# SX1308_GTW_e381v02c_RF_Part.net
KiCad netlist of a schematic drawn in Altium Designer
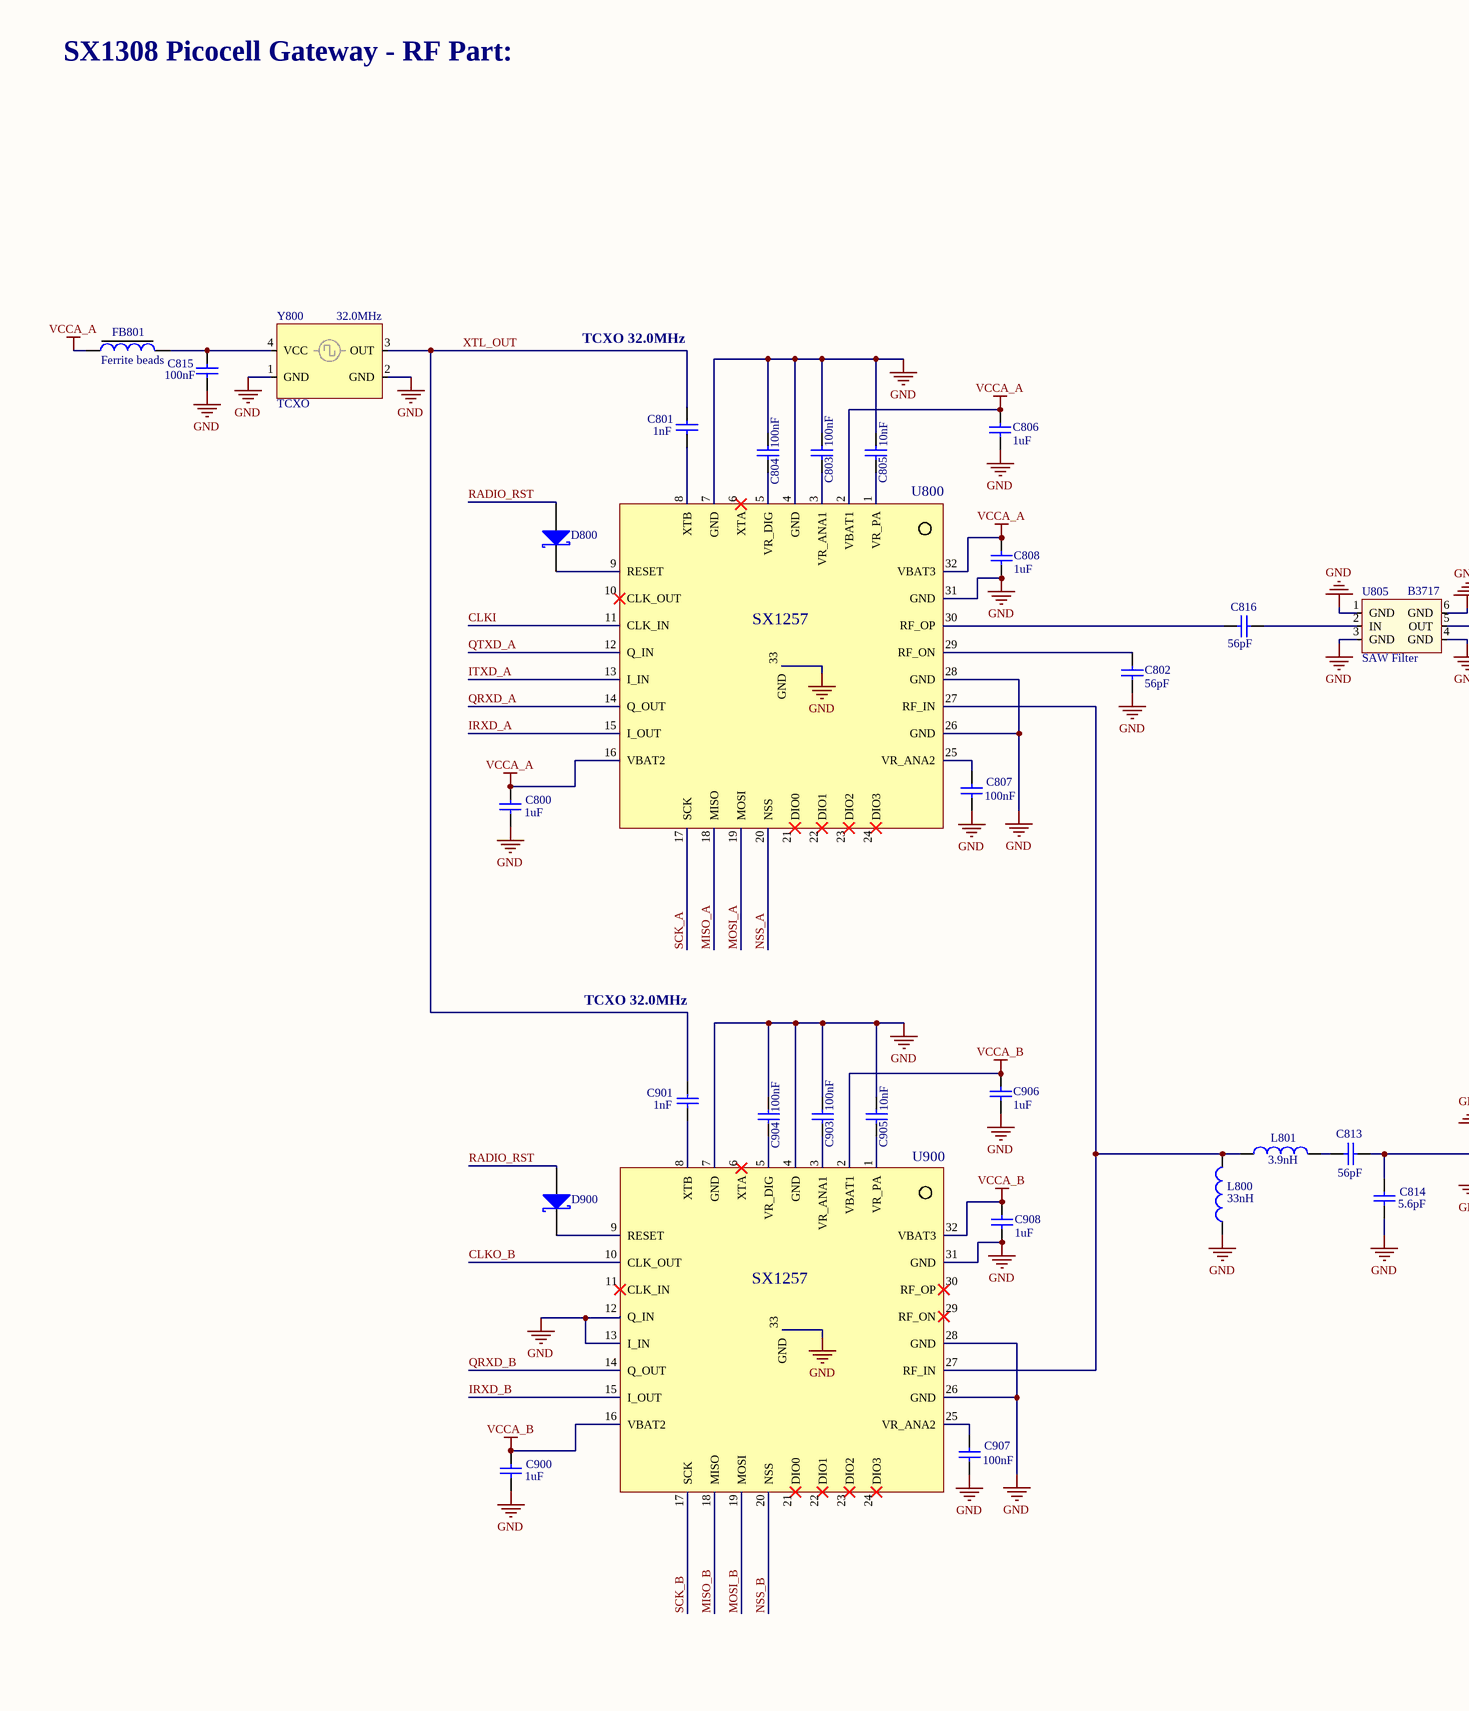
[diagram p0: SX1308_GTW_e381v02c_RF_Part.SchDoc, left]
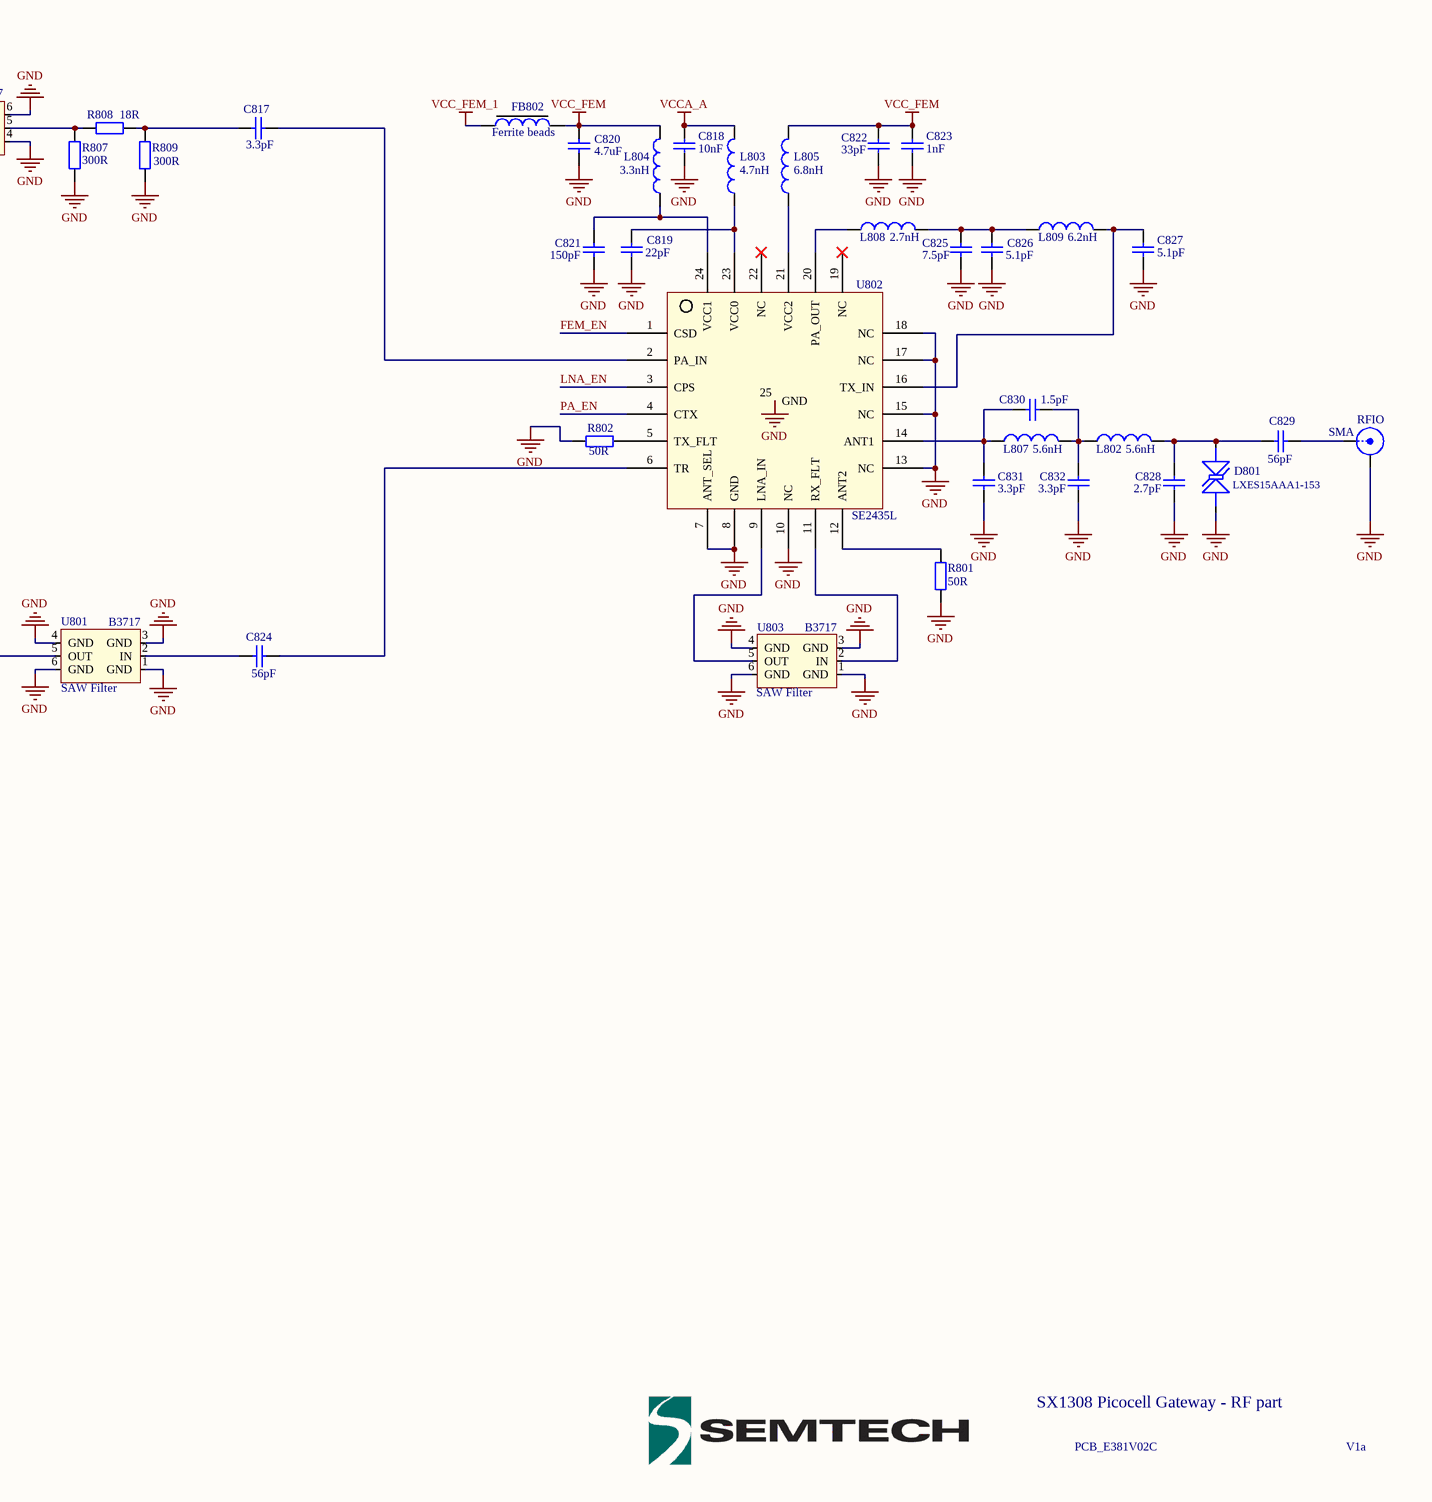
[diagram p1: SX1308_GTW_e381v02c_RF_Part.SchDoc, right]

(export (version "E")
  (design (tool "Eeschema 10.0.6"))
  (components
    (comp (ref "C800")
      (value "1uF")
      (footprint "rlc_603_smd")
      (description "Capacitor SMD")
      (fields (field (name "Comment") "Cap") (field (name "PUBLISHER") "Altium Limited"))
      (libsource (lib "SX1308_GTW_e381v02c") (part "Cap"))
    )
    (comp (ref "C801")
      (value "1nF")
      (footprint "rlc_402_smd")
      (description "Capacitor SMD")
      (fields (field (name "Comment") "Cap") (field (name "PUBLISHER") "Altium Limited"))
      (libsource (lib "SX1308_GTW_e381v02c") (part "Cap"))
    )
    (comp (ref "C802")
      (value "56pF")
      (footprint "rlc_402_smd")
      (description "Capacitor SMD")
      (fields (field (name "Comment") "Cap") (field (name "PUBLISHER") "Altium Limited"))
      (libsource (lib "SX1308_GTW_e381v02c") (part "Cap"))
    )
    (comp (ref "C803")
      (value "100nF")
      (footprint "rlc_402_smd")
      (description "Capacitor SMD")
      (fields (field (name "Comment") "Cap") (field (name "PUBLISHER") "Altium Limited"))
      (libsource (lib "SX1308_GTW_e381v02c") (part "Cap"))
    )
    (comp (ref "C804")
      (value "100nF")
      (footprint "rlc_402_smd")
      (description "Capacitor SMD")
      (fields (field (name "Comment") "Cap") (field (name "PUBLISHER") "Altium Limited"))
      (libsource (lib "SX1308_GTW_e381v02c") (part "Cap"))
    )
    (comp (ref "C805")
      (value "10nF")
      (footprint "rlc_402_smd")
      (description "Capacitor SMD")
      (fields (field (name "Comment") "Cap") (field (name "PUBLISHER") "Altium Limited"))
      (libsource (lib "SX1308_GTW_e381v02c") (part "Cap"))
    )
    (comp (ref "C806")
      (value "1uF")
      (footprint "rlc_603_smd")
      (description "Capacitor SMD")
      (fields (field (name "Comment") "Cap") (field (name "PUBLISHER") "Altium Limited"))
      (libsource (lib "SX1308_GTW_e381v02c") (part "Cap"))
    )
    (comp (ref "C807")
      (value "100nF")
      (footprint "rlc_402_smd")
      (description "Capacitor SMD")
      (fields (field (name "Comment") "Cap") (field (name "PUBLISHER") "Altium Limited"))
      (libsource (lib "SX1308_GTW_e381v02c") (part "Cap"))
    )
    (comp (ref "C808")
      (value "1uF")
      (footprint "rlc_603_smd")
      (description "Capacitor SMD")
      (fields (field (name "Comment") "Cap") (field (name "PUBLISHER") "Altium Limited"))
      (libsource (lib "SX1308_GTW_e381v02c") (part "Cap"))
    )
    (comp (ref "C813")
      (value "56pF")
      (footprint "rlc_402_smd")
      (description "Capacitor SMD")
      (fields (field (name "Comment") "Cap") (field (name "PUBLISHER") "Altium Limited"))
      (libsource (lib "SX1308_GTW_e381v02c") (part "Cap"))
    )
    (comp (ref "C814")
      (value "5.6pF")
      (footprint "rlc_402_smd")
      (description "Capacitor SMD")
      (fields (field (name "Comment") "Cap") (field (name "PUBLISHER") "Altium Limited"))
      (libsource (lib "SX1308_GTW_e381v02c") (part "Cap"))
    )
    (comp (ref "C815")
      (value "100nF")
      (footprint "rlc_402_smd")
      (description "Capacitor SMD")
      (fields (field (name "Comment") "Cap") (field (name "PUBLISHER") "Altium Limited"))
      (libsource (lib "SX1308_GTW_e381v02c") (part "Cap"))
    )
    (comp (ref "C816")
      (value "56pF")
      (footprint "rlc_402_smd")
      (description "Capacitor SMD")
      (fields (field (name "Comment") "Cap") (field (name "PUBLISHER") "Altium Limited"))
      (libsource (lib "SX1308_GTW_e381v02c") (part "Cap"))
    )
    (comp (ref "C817")
      (value "3.3pF")
      (footprint "rlc_402_smd")
      (description "Capacitor SMD")
      (fields (field (name "Comment") "Cap") (field (name "PUBLISHER") "Altium Limited"))
      (libsource (lib "SX1308_GTW_e381v02c") (part "Cap"))
    )
    (comp (ref "C818")
      (value "10nF")
      (footprint "rlc_402_smd")
      (description "Capacitor SMD")
      (fields (field (name "Comment") "Cap") (field (name "PUBLISHER") "Altium Limited"))
      (libsource (lib "SX1308_GTW_e381v02c") (part "Cap"))
    )
    (comp (ref "C819")
      (value "22pF")
      (footprint "rlc_402_smd")
      (description "Capacitor SMD")
      (fields (field (name "Comment") "Cap") (field (name "PUBLISHER") "Altium Limited"))
      (libsource (lib "SX1308_GTW_e381v02c") (part "Cap"))
    )
    (comp (ref "C820")
      (value "4.7uF")
      (footprint "rlc_603_smd")
      (description "Capacitor SMD")
      (fields (field (name "Comment") "Cap") (field (name "PUBLISHER") "Altium Limited"))
      (libsource (lib "SX1308_GTW_e381v02c") (part "Cap"))
    )
    (comp (ref "C821")
      (value "150pF")
      (footprint "rlc_402_smd")
      (description "Capacitor SMD")
      (fields (field (name "Comment") "Cap") (field (name "PUBLISHER") "Altium Limited"))
      (libsource (lib "SX1308_GTW_e381v02c") (part "Cap"))
    )
    (comp (ref "C822")
      (value "33pF")
      (footprint "rlc_402_smd")
      (description "Capacitor SMD")
      (fields (field (name "Comment") "Cap") (field (name "PUBLISHER") "Altium Limited"))
      (libsource (lib "SX1308_GTW_e381v02c") (part "Cap"))
    )
    (comp (ref "C823")
      (value "1nF")
      (footprint "rlc_402_smd")
      (description "Capacitor SMD")
      (fields (field (name "Comment") "Cap") (field (name "PUBLISHER") "Altium Limited"))
      (libsource (lib "SX1308_GTW_e381v02c") (part "Cap"))
    )
    (comp (ref "C824")
      (value "56pF")
      (footprint "rlc_402_smd")
      (description "Capacitor SMD")
      (fields (field (name "Comment") "Cap") (field (name "PUBLISHER") "Altium Limited"))
      (libsource (lib "SX1308_GTW_e381v02c") (part "Cap"))
    )
    (comp (ref "C825")
      (value "7.5pF")
      (footprint "rlc_402_smd")
      (description "Capacitor SMD")
      (fields (field (name "Comment") "Cap") (field (name "PUBLISHER") "Altium Limited"))
      (libsource (lib "SX1308_GTW_e381v02c") (part "Cap"))
    )
    (comp (ref "C826")
      (value "5.1pF")
      (footprint "rlc_402_smd")
      (description "Capacitor SMD")
      (fields (field (name "Comment") "Cap") (field (name "PUBLISHER") "Altium Limited"))
      (libsource (lib "SX1308_GTW_e381v02c") (part "Cap"))
    )
    (comp (ref "C827")
      (value "5.1pF")
      (footprint "rlc_402_smd")
      (description "Capacitor SMD")
      (fields (field (name "Comment") "Cap") (field (name "PUBLISHER") "Altium Limited"))
      (libsource (lib "SX1308_GTW_e381v02c") (part "Cap"))
    )
    (comp (ref "C828")
      (value "2.7pF")
      (footprint "rlc_402_smd")
      (description "Capacitor SMD")
      (fields (field (name "Comment") "Cap") (field (name "PUBLISHER") "Altium Limited"))
      (libsource (lib "SX1308_GTW_e381v02c") (part "Cap"))
    )
    (comp (ref "C829")
      (value "56pF")
      (footprint "rlc_402_smd")
      (description "Capacitor SMD")
      (fields (field (name "Comment") "Cap") (field (name "PUBLISHER") "Altium Limited"))
      (libsource (lib "SX1308_GTW_e381v02c") (part "Cap"))
    )
    (comp (ref "C830")
      (value "1.5pF")
      (footprint "rlc_402_smd")
      (description "Capacitor SMD")
      (fields (field (name "Comment") "Cap") (field (name "PUBLISHER") "Altium Limited"))
      (libsource (lib "SX1308_GTW_e381v02c") (part "Cap"))
    )
    (comp (ref "C831")
      (value "3.3pF")
      (footprint "rlc_402_smd")
      (description "Capacitor SMD")
      (fields (field (name "Comment") "Cap") (field (name "PUBLISHER") "Altium Limited"))
      (libsource (lib "SX1308_GTW_e381v02c") (part "Cap"))
    )
    (comp (ref "C832")
      (value "3.3pF")
      (footprint "rlc_402_smd")
      (description "Capacitor SMD")
      (fields (field (name "Comment") "Cap") (field (name "PUBLISHER") "Altium Limited"))
      (libsource (lib "SX1308_GTW_e381v02c") (part "Cap"))
    )
    (comp (ref "C900")
      (value "1uF")
      (footprint "rlc_603_smd")
      (description "Capacitor SMD")
      (fields (field (name "Comment") "Cap") (field (name "PUBLISHER") "Altium Limited"))
      (libsource (lib "SX1308_GTW_e381v02c") (part "Cap"))
    )
    (comp (ref "C901")
      (value "1nF")
      (footprint "rlc_402_smd")
      (description "Capacitor SMD")
      (fields (field (name "Comment") "Cap") (field (name "PUBLISHER") "Altium Limited"))
      (libsource (lib "SX1308_GTW_e381v02c") (part "Cap"))
    )
    (comp (ref "C903")
      (value "100nF")
      (footprint "rlc_402_smd")
      (description "Capacitor SMD")
      (fields (field (name "Comment") "Cap") (field (name "PUBLISHER") "Altium Limited"))
      (libsource (lib "SX1308_GTW_e381v02c") (part "Cap"))
    )
    (comp (ref "C904")
      (value "100nF")
      (footprint "rlc_402_smd")
      (description "Capacitor SMD")
      (fields (field (name "Comment") "Cap") (field (name "PUBLISHER") "Altium Limited"))
      (libsource (lib "SX1308_GTW_e381v02c") (part "Cap"))
    )
    (comp (ref "C905")
      (value "10nF")
      (footprint "rlc_402_smd")
      (description "Capacitor SMD")
      (fields (field (name "Comment") "Cap") (field (name "PUBLISHER") "Altium Limited"))
      (libsource (lib "SX1308_GTW_e381v02c") (part "Cap"))
    )
    (comp (ref "C906")
      (value "1uF")
      (footprint "rlc_603_smd")
      (description "Capacitor SMD")
      (fields (field (name "Comment") "Cap") (field (name "PUBLISHER") "Altium Limited"))
      (libsource (lib "SX1308_GTW_e381v02c") (part "Cap"))
    )
    (comp (ref "C907")
      (value "100nF")
      (footprint "rlc_402_smd")
      (description "Capacitor SMD")
      (fields (field (name "Comment") "Cap") (field (name "PUBLISHER") "Altium Limited"))
      (libsource (lib "SX1308_GTW_e381v02c") (part "Cap"))
    )
    (comp (ref "C908")
      (value "1uF")
      (footprint "rlc_603_smd")
      (description "Capacitor SMD")
      (fields (field (name "Comment") "Cap") (field (name "PUBLISHER") "Altium Limited"))
      (libsource (lib "SX1308_GTW_e381v02c") (part "Cap"))
    )
    (comp (ref "D800")
      (value "D Schottky")
      (footprint "SOD523")
      (description "Schottky Diode")
      (fields (field (name "PUBLISHER") "Altium Limited"))
      (libsource (lib "SX1308_GTW_e381v02c") (part "D Schottky"))
    )
    (comp (ref "D801")
      (value "RClamp0531T")
      (footprint "SLP1006P2T")
      (description "Ultra Low Capacitance 1-line ESD Protection")
      (fields (field (name "TYPE") "LXES15AAA1-153"))
      (libsource (lib "SX1308_GTW_e381v02c") (part "RClamp0531T"))
    )
    (comp (ref "D900")
      (value "D Schottky")
      (footprint "SOD523")
      (description "Schottky Diode")
      (fields (field (name "PUBLISHER") "Altium Limited"))
      (libsource (lib "SX1308_GTW_e381v02c") (part "D Schottky"))
    )
    (comp (ref "FB801")
      (value "Ferrite beads")
      (footprint "rlc_402_smd")
      (libsource (lib "SX1308_GTW_e381v02c") (part "Ferrite beads"))
    )
    (comp (ref "FB802")
      (value "Ferrite beads")
      (footprint "rlc_603_smd")
      (libsource (lib "SX1308_GTW_e381v02c") (part "Ferrite beads"))
    )
    (comp (ref "L800")
      (value "33nH")
      (footprint "rlc_402_smd")
      (description "Inductor")
      (fields (field (name "PUBLISHER") "Altium Limited"))
      (libsource (lib "SX1308_GTW_e381v02c") (part "Inductor"))
    )
    (comp (ref "L801")
      (value "3.9nH")
      (footprint "rlc_402_smd")
      (description "Inductor")
      (fields (field (name "PUBLISHER") "Altium Limited"))
      (libsource (lib "SX1308_GTW_e381v02c") (part "Inductor"))
    )
    (comp (ref "L802")
      (value "5.6nH")
      (footprint "rlc_402_smd")
      (description "Inductor")
      (fields (field (name "PUBLISHER") "Altium Limited"))
      (libsource (lib "SX1308_GTW_e381v02c") (part "Inductor"))
    )
    (comp (ref "L803")
      (value "4.7nH")
      (footprint "rlc_402_smd")
      (description "Inductor")
      (fields (field (name "PUBLISHER") "Altium Limited"))
      (libsource (lib "SX1308_GTW_e381v02c") (part "Inductor"))
    )
    (comp (ref "L804")
      (value "3.3nH")
      (footprint "rlc_402_smd")
      (description "Inductor")
      (fields (field (name "PUBLISHER") "Altium Limited"))
      (libsource (lib "SX1308_GTW_e381v02c") (part "Inductor"))
    )
    (comp (ref "L805")
      (value "6.8nH")
      (footprint "rlc_402_smd")
      (description "Inductor")
      (fields (field (name "PUBLISHER") "Altium Limited"))
      (libsource (lib "SX1308_GTW_e381v02c") (part "Inductor"))
    )
    (comp (ref "L807")
      (value "5.6nH")
      (footprint "rlc_402_smd")
      (description "Inductor")
      (fields (field (name "PUBLISHER") "Altium Limited"))
      (libsource (lib "SX1308_GTW_e381v02c") (part "Inductor"))
    )
    (comp (ref "L808")
      (value "2.7nH")
      (footprint "rlc_402_smd")
      (description "Inductor")
      (fields (field (name "PUBLISHER") "Altium Limited"))
      (libsource (lib "SX1308_GTW_e381v02c") (part "Inductor"))
    )
    (comp (ref "L809")
      (value "6.2nH")
      (footprint "rlc_402_smd")
      (description "Inductor")
      (fields (field (name "PUBLISHER") "Altium Limited"))
      (libsource (lib "SX1308_GTW_e381v02c") (part "Inductor"))
    )
    (comp (ref "R801")
      (value "50R")
      (footprint "rlc_402_smd")
      (description "Resistor SMD - IEC symbol version")
      (fields (field (name "Comment") "Resistor"))
      (libsource (lib "") (part "Resistor_3"))
    )
    (comp (ref "R802")
      (value "50R")
      (footprint "rlc_402_smd")
      (description "Resistor SMD - IEC symbol version")
      (fields (field (name "Comment") "Resistor"))
      (libsource (lib "") (part "Resistor_2"))
    )
    (comp (ref "R807")
      (value "300R")
      (footprint "rlc_402_smd")
      (description "Resistor SMD - IEC symbol version")
      (fields (field (name "Comment") "Resistor"))
      (libsource (lib "") (part "Resistor_1"))
    )
    (comp (ref "R808")
      (value "18R")
      (footprint "rlc_402_smd")
      (description "Resistor SMD - IEC symbol version")
      (fields (field (name "Comment") "Resistor"))
      (libsource (lib "SX1308_GTW_e381v02c") (part "Resistor"))
    )
    (comp (ref "R809")
      (value "300R")
      (footprint "rlc_402_smd")
      (description "Resistor SMD - IEC symbol version")
      (fields (field (name "Comment") "Resistor"))
      (libsource (lib "") (part "Resistor_1"))
    )
    (comp (ref "RFIO")
      (value "SMA")
      (footprint "SMA_end_launch_1.6mm_6.35mm")
      (description "SMA Straight Connector")
      (fields (field (name "PUBLISHER") "Altium Limited"))
      (libsource (lib "SX1308_GTW_e381v02c") (part "SMA"))
    )
    (comp (ref "U800")
      (value "SX1257")
      (footprint "vqfn32_5x5mm")
      (description "SX1257 RF Front-End Transceiver - I/Q New Pinout")
      (libsource (lib "SX1308_GTW_e381v02c") (part "SX1257"))
    )
    (comp (ref "U801")
      (value "SAW Filter")
      (footprint "DCC6C_3.0x3.0mm")
      (description "SAW Filter - Bandpass - TEMEX type")
      (fields (field (name "ALTIUM_VALUE") "B3717"))
      (libsource (lib "SX1308_GTW_e381v02c") (part "SAW Filter"))
    )
    (comp (ref "U802")
      (value "SE2435L")
      (footprint "vqfn24_4x4mm RF")
      (description "SE2435L - Skyworks High Power RF Front End Module")
      (libsource (lib "SX1308_GTW_e381v02c") (part "SE2435L"))
    )
    (comp (ref "U803")
      (value "SAW Filter")
      (footprint "DCC6C_3.0x3.0mm")
      (description "SAW Filter - Bandpass - TEMEX type")
      (fields (field (name "ALTIUM_VALUE") "B3717"))
      (libsource (lib "SX1308_GTW_e381v02c") (part "SAW Filter"))
    )
    (comp (ref "U805")
      (value "SAW Filter")
      (footprint "DCC6C_3.0x3.0mm")
      (description "SAW Filter - Bandpass - TEMEX type")
      (fields (field (name "ALTIUM_VALUE") "B3717"))
      (libsource (lib "") (part "SAW Filter_1"))
    )
    (comp (ref "U900")
      (value "SX1257")
      (footprint "vqfn32_5x5mm")
      (description "SX1257 RF Front-End Transceiver - I/Q New Pinout")
      (libsource (lib "SX1308_GTW_e381v02c") (part "SX1257"))
    )
    (comp (ref "Y800")
      (value "TCXO")
      (footprint "TCXO 2.0x1.6mm")
      (fields (field (name "ALTIUM_VALUE") "32.0MHz"))
      (libsource (lib "SX1308_GTW_e381v02c") (part "TCXO"))
    )
  )
  (nets
    (net (code "1") (name "/CLKI") (class "Default")
      (node (ref "U800") (pin "11") (pinfunction "CLK_IN_11") (pintype "passive"))
    )
    (net (code "2") (name "/CLKO_B") (class "Default")
      (node (ref "U900") (pin "10") (pinfunction "CLK_OUT_10") (pintype "passive"))
    )
    (net (code "3") (name "/FEM_EN") (class "Default")
      (node (ref "U802") (pin "1") (pinfunction "CSD_1") (pintype "passive"))
    )
    (net (code "4") (name "/IRXD_A") (class "Default")
      (node (ref "U800") (pin "15") (pinfunction "I_OUT_15") (pintype "passive"))
    )
    (net (code "5") (name "/IRXD_B") (class "Default")
      (node (ref "U900") (pin "15") (pinfunction "I_OUT_15") (pintype "passive"))
    )
    (net (code "6") (name "/ITXD_A") (class "Default")
      (node (ref "U800") (pin "13") (pinfunction "I_IN_13") (pintype "passive"))
    )
    (net (code "7") (name "/LNA_EN") (class "Default")
      (node (ref "U802") (pin "3") (pinfunction "CPS_3") (pintype "passive"))
    )
    (net (code "8") (name "/MISO_A") (class "Default")
      (node (ref "U800") (pin "18") (pinfunction "MISO_18") (pintype "passive"))
    )
    (net (code "9") (name "/MISO_B") (class "Default")
      (node (ref "U900") (pin "18") (pinfunction "MISO_18") (pintype "passive"))
    )
    (net (code "10") (name "/MOSI_A") (class "Default")
      (node (ref "U800") (pin "19") (pinfunction "MOSI_19") (pintype "passive"))
    )
    (net (code "11") (name "/MOSI_B") (class "Default")
      (node (ref "U900") (pin "19") (pinfunction "MOSI_19") (pintype "passive"))
    )
    (net (code "12") (name "/NSS_A") (class "Default")
      (node (ref "U800") (pin "20") (pinfunction "NSS_20") (pintype "passive"))
    )
    (net (code "13") (name "/NSS_B") (class "Default")
      (node (ref "U900") (pin "20") (pinfunction "NSS_20") (pintype "passive"))
    )
    (net (code "14") (name "/PA_EN") (class "Default")
      (node (ref "U802") (pin "4") (pinfunction "CTX_4") (pintype "passive"))
    )
    (net (code "15") (name "/QRXD_A") (class "Default")
      (node (ref "U800") (pin "14") (pinfunction "Q_OUT_14") (pintype "passive"))
    )
    (net (code "16") (name "/QRXD_B") (class "Default")
      (node (ref "U900") (pin "14") (pinfunction "Q_OUT_14") (pintype "passive"))
    )
    (net (code "17") (name "/QTXD_A") (class "Default")
      (node (ref "U800") (pin "12") (pinfunction "Q_IN_12") (pintype "passive"))
    )
    (net (code "18") (name "/RADIO_RST") (class "Default")
      (node (ref "D800") (pin "2") (pinfunction "A_2") (pintype "passive"))
      (node (ref "D900") (pin "2") (pinfunction "A_2") (pintype "passive"))
    )
    (net (code "19") (name "/SCK_A") (class "Default")
      (node (ref "U800") (pin "17") (pinfunction "SCK_17") (pintype "passive"))
    )
    (net (code "20") (name "/SCK_B") (class "Default")
      (node (ref "U900") (pin "17") (pinfunction "SCK_17") (pintype "passive"))
    )
    (net (code "21") (name "/XTL_OUT") (class "Default")
      (node (ref "C801") (pin "1") (pinfunction "1_1") (pintype "passive"))
      (node (ref "C901") (pin "2") (pinfunction "2_2") (pintype "passive"))
      (node (ref "Y800") (pin "3") (pinfunction "OUT_3") (pintype "passive"))
    )
    (net (code "22") (name "GND") (class "Default")
      (node (ref "C800") (pin "1") (pinfunction "1_1") (pintype "passive"))
      (node (ref "C802") (pin "2") (pinfunction "2_2") (pintype "passive"))
      (node (ref "C803") (pin "1") (pinfunction "1_1") (pintype "passive"))
      (node (ref "C804") (pin "2") (pinfunction "2_2") (pintype "passive"))
      (node (ref "C805") (pin "2") (pinfunction "2_2") (pintype "passive"))
      (node (ref "C806") (pin "1") (pinfunction "1_1") (pintype "passive"))
      (node (ref "C807") (pin "1") (pinfunction "1_1") (pintype "passive"))
      (node (ref "C808") (pin "1") (pinfunction "1_1") (pintype "passive"))
      (node (ref "C814") (pin "2") (pinfunction "2_2") (pintype "passive"))
      (node (ref "C815") (pin "1") (pinfunction "1_1") (pintype "passive"))
      (node (ref "C818") (pin "1") (pinfunction "1_1") (pintype "passive"))
      (node (ref "C819") (pin "1") (pinfunction "1_1") (pintype "passive"))
      (node (ref "C820") (pin "1") (pinfunction "1_1") (pintype "passive"))
      (node (ref "C821") (pin "1") (pinfunction "1_1") (pintype "passive"))
      (node (ref "C822") (pin "1") (pinfunction "1_1") (pintype "passive"))
      (node (ref "C823") (pin "1") (pinfunction "1_1") (pintype "passive"))
      (node (ref "C825") (pin "1") (pinfunction "1_1") (pintype "passive"))
      (node (ref "C826") (pin "1") (pinfunction "1_1") (pintype "passive"))
      (node (ref "C827") (pin "1") (pinfunction "1_1") (pintype "passive"))
      (node (ref "C828") (pin "2") (pinfunction "2_2") (pintype "passive"))
      (node (ref "C831") (pin "1") (pinfunction "1_1") (pintype "passive"))
      (node (ref "C832") (pin "2") (pinfunction "2_2") (pintype "passive"))
      (node (ref "C900") (pin "1") (pinfunction "1_1") (pintype "passive"))
      (node (ref "C903") (pin "1") (pinfunction "1_1") (pintype "passive"))
      (node (ref "C904") (pin "2") (pinfunction "2_2") (pintype "passive"))
      (node (ref "C905") (pin "2") (pinfunction "2_2") (pintype "passive"))
      (node (ref "C906") (pin "1") (pinfunction "1_1") (pintype "passive"))
      (node (ref "C907") (pin "1") (pinfunction "1_1") (pintype "passive"))
      (node (ref "C908") (pin "1") (pinfunction "1_1") (pintype "passive"))
      (node (ref "D801") (pin "2") (pinfunction "K_2") (pintype "passive"))
      (node (ref "L800") (pin "1") (pinfunction "1_1") (pintype "passive"))
      (node (ref "R801") (pin "2") (pinfunction "2_2") (pintype "passive"))
      (node (ref "R802") (pin "2") (pinfunction "2_2") (pintype "passive"))
      (node (ref "R807") (pin "1") (pinfunction "1_1") (pintype "passive"))
      (node (ref "R809") (pin "1") (pinfunction "1_1") (pintype "passive"))
      (node (ref "RFIO") (pin "2") (pinfunction "GND_2") (pintype "passive"))
      (node (ref "U800") (pin "26") (pinfunction "GND_26") (pintype "passive"))
      (node (ref "U800") (pin "28") (pinfunction "GND_28") (pintype "passive"))
      (node (ref "U800") (pin "31") (pinfunction "GND_31") (pintype "passive"))
      (node (ref "U800") (pin "33") (pinfunction "GND_33") (pintype "passive"))
      (node (ref "U800") (pin "4") (pinfunction "GND_4") (pintype "passive"))
      (node (ref "U800") (pin "7") (pinfunction "GND_7") (pintype "passive"))
      (node (ref "U801") (pin "1") (pinfunction "GND_1") (pintype "passive"))
      (node (ref "U801") (pin "3") (pinfunction "GND_3") (pintype "passive"))
      (node (ref "U801") (pin "4") (pinfunction "GND_4") (pintype "passive"))
      (node (ref "U801") (pin "6") (pinfunction "GND_6") (pintype "passive"))
      (node (ref "U802") (pin "10") (pinfunction "NC_10") (pintype "passive"))
      (node (ref "U802") (pin "13") (pinfunction "NC_13") (pintype "passive"))
      (node (ref "U802") (pin "15") (pinfunction "NC_15") (pintype "passive"))
      (node (ref "U802") (pin "17") (pinfunction "NC_17") (pintype "passive"))
      (node (ref "U802") (pin "18") (pinfunction "NC_18") (pintype "passive"))
      (node (ref "U802") (pin "25") (pinfunction "GND_25") (pintype "passive"))
      (node (ref "U802") (pin "7") (pinfunction "ANT_SEL_7") (pintype "passive"))
      (node (ref "U802") (pin "8") (pinfunction "GND_8") (pintype "passive"))
      (node (ref "U803") (pin "1") (pinfunction "GND_1") (pintype "passive"))
      (node (ref "U803") (pin "3") (pinfunction "GND_3") (pintype "passive"))
      (node (ref "U803") (pin "4") (pinfunction "GND_4") (pintype "passive"))
      (node (ref "U803") (pin "6") (pinfunction "GND_6") (pintype "passive"))
      (node (ref "U805") (pin "1") (pinfunction "GND_1") (pintype "passive"))
      (node (ref "U805") (pin "3") (pinfunction "GND_3") (pintype "passive"))
      (node (ref "U805") (pin "4") (pinfunction "GND_4") (pintype "passive"))
      (node (ref "U805") (pin "6") (pinfunction "GND_6") (pintype "passive"))
      (node (ref "U900") (pin "12") (pinfunction "Q_IN_12") (pintype "passive"))
      (node (ref "U900") (pin "13") (pinfunction "I_IN_13") (pintype "passive"))
      (node (ref "U900") (pin "26") (pinfunction "GND_26") (pintype "passive"))
      (node (ref "U900") (pin "28") (pinfunction "GND_28") (pintype "passive"))
      (node (ref "U900") (pin "31") (pinfunction "GND_31") (pintype "passive"))
      (node (ref "U900") (pin "33") (pinfunction "GND_33") (pintype "passive"))
      (node (ref "U900") (pin "4") (pinfunction "GND_4") (pintype "passive"))
      (node (ref "U900") (pin "7") (pinfunction "GND_7") (pintype "passive"))
      (node (ref "Y800") (pin "1") (pinfunction "GND_1") (pintype "passive"))
      (node (ref "Y800") (pin "2") (pinfunction "GND_2") (pintype "passive"))
    )
    (net (code "23") (name "Net-(C813-Pad1)") (class "Default")
      (node (ref "C813") (pin "1") (pinfunction "1_1") (pintype "passive"))
      (node (ref "L801") (pin "2") (pinfunction "2_2") (pintype "passive"))
    )
    (net (code "24") (name "Net-(C817-Pad1)") (class "Default")
      (node (ref "C817") (pin "1") (pinfunction "1_1") (pintype "passive"))
      (node (ref "R808") (pin "2") (pinfunction "2_2") (pintype "passive"))
      (node (ref "R809") (pin "2") (pinfunction "2_2") (pintype "passive"))
    )
    (net (code "25") (name "Net-(C825-Pad2)") (class "Default")
      (node (ref "C825") (pin "2") (pinfunction "2_2") (pintype "passive"))
      (node (ref "C826") (pin "2") (pinfunction "2_2") (pintype "passive"))
      (node (ref "L808") (pin "2") (pinfunction "2_2") (pintype "passive"))
      (node (ref "L809") (pin "1") (pinfunction "1_1") (pintype "passive"))
    )
    (net (code "26") (name "Net-(C830-Pad1)") (class "Default")
      (node (ref "C830") (pin "1") (pinfunction "1_1") (pintype "passive"))
      (node (ref "C832") (pin "1") (pinfunction "1_1") (pintype "passive"))
      (node (ref "L802") (pin "1") (pinfunction "1_1") (pintype "passive"))
      (node (ref "L807") (pin "2") (pinfunction "2_2") (pintype "passive"))
    )
    (net (code "27") (name "Net-(D800-K)") (class "Default")
      (node (ref "D800") (pin "1") (pinfunction "K_1") (pintype "passive"))
      (node (ref "U800") (pin "9") (pinfunction "RESET_9") (pintype "passive"))
    )
    (net (code "28") (name "Net-(D801-A)") (class "Default")
      (node (ref "C828") (pin "1") (pinfunction "1_1") (pintype "passive"))
      (node (ref "C829") (pin "1") (pinfunction "1_1") (pintype "passive"))
      (node (ref "D801") (pin "1") (pinfunction "A_1") (pintype "passive"))
      (node (ref "L802") (pin "2") (pinfunction "2_2") (pintype "passive"))
    )
    (net (code "29") (name "Net-(D900-K)") (class "Default")
      (node (ref "D900") (pin "1") (pinfunction "K_1") (pintype "passive"))
      (node (ref "U900") (pin "9") (pinfunction "RESET_9") (pintype "passive"))
    )
    (net (code "30") (name "Net-(RFIO-Signal)") (class "Default")
      (node (ref "C829") (pin "2") (pinfunction "2_2") (pintype "passive"))
      (node (ref "RFIO") (pin "1") (pinfunction "Signal_1") (pintype "passive"))
    )
    (net (code "31") (name "Net-(U800-RF_IN)") (class "Default")
      (node (ref "L800") (pin "2") (pinfunction "2_2") (pintype "passive"))
      (node (ref "L801") (pin "1") (pinfunction "1_1") (pintype "passive"))
      (node (ref "U800") (pin "27") (pinfunction "RF_IN_27") (pintype "passive"))
      (node (ref "U900") (pin "27") (pinfunction "RF_IN_27") (pintype "passive"))
    )
    (net (code "32") (name "Net-(U800-RF_ON)") (class "Default")
      (node (ref "C802") (pin "1") (pinfunction "1_1") (pintype "passive"))
      (node (ref "U800") (pin "29") (pinfunction "RF_ON_29") (pintype "passive"))
    )
    (net (code "33") (name "Net-(U800-RF_OP)") (class "Default")
      (node (ref "C816") (pin "1") (pinfunction "1_1") (pintype "passive"))
      (node (ref "U800") (pin "30") (pinfunction "RF_OP_30") (pintype "passive"))
    )
    (net (code "34") (name "Net-(U800-VR_ANA1)") (class "Default")
      (node (ref "C803") (pin "2") (pinfunction "2_2") (pintype "passive"))
      (node (ref "U800") (pin "3") (pinfunction "VR_ANA1_3") (pintype "passive"))
    )
    (net (code "35") (name "Net-(U800-VR_ANA2)") (class "Default")
      (node (ref "C807") (pin "2") (pinfunction "2_2") (pintype "passive"))
      (node (ref "U800") (pin "25") (pinfunction "VR_ANA2_25") (pintype "passive"))
    )
    (net (code "36") (name "Net-(U800-VR_DIG)") (class "Default")
      (node (ref "C804") (pin "1") (pinfunction "1_1") (pintype "passive"))
      (node (ref "U800") (pin "5") (pinfunction "VR_DIG_5") (pintype "passive"))
    )
    (net (code "37") (name "Net-(U800-VR_PA)") (class "Default")
      (node (ref "C805") (pin "1") (pinfunction "1_1") (pintype "passive"))
      (node (ref "U800") (pin "1") (pinfunction "VR_PA_1") (pintype "passive"))
    )
    (net (code "38") (name "Net-(U800-XTB)") (class "Default")
      (node (ref "C801") (pin "2") (pinfunction "2_2") (pintype "passive"))
      (node (ref "U800") (pin "8") (pinfunction "XTB_8") (pintype "passive"))
    )
    (net (code "39") (name "Net-(U801-IN)") (class "Default")
      (node (ref "C824") (pin "1") (pinfunction "1_1") (pintype "passive"))
      (node (ref "U801") (pin "2") (pinfunction "IN_2") (pintype "passive"))
    )
    (net (code "40") (name "Net-(U801-OUT)") (class "Default")
      (node (ref "C813") (pin "2") (pinfunction "2_2") (pintype "passive"))
      (node (ref "C814") (pin "1") (pinfunction "1_1") (pintype "passive"))
      (node (ref "U801") (pin "5") (pinfunction "OUT_5") (pintype "passive"))
    )
    (net (code "41") (name "Net-(U802-ANT1)") (class "Default")
      (node (ref "C830") (pin "2") (pinfunction "2_2") (pintype "passive"))
      (node (ref "C831") (pin "2") (pinfunction "2_2") (pintype "passive"))
      (node (ref "L807") (pin "1") (pinfunction "1_1") (pintype "passive"))
      (node (ref "U802") (pin "14") (pinfunction "ANT1_14") (pintype "passive"))
    )
    (net (code "42") (name "Net-(U802-ANT2)") (class "Default")
      (node (ref "R801") (pin "1") (pinfunction "1_1") (pintype "passive"))
      (node (ref "U802") (pin "12") (pinfunction "ANT2_12") (pintype "passive"))
    )
    (net (code "43") (name "Net-(U802-LNA_IN)") (class "Default")
      (node (ref "U802") (pin "9") (pinfunction "LNA_IN_9") (pintype "passive"))
      (node (ref "U803") (pin "5") (pinfunction "OUT_5") (pintype "passive"))
    )
    (net (code "44") (name "Net-(U802-PA_IN)") (class "Default")
      (node (ref "C817") (pin "2") (pinfunction "2_2") (pintype "passive"))
      (node (ref "U802") (pin "2") (pinfunction "PA_IN_2") (pintype "passive"))
    )
    (net (code "45") (name "Net-(U802-PA_OUT)") (class "Default")
      (node (ref "L808") (pin "1") (pinfunction "1_1") (pintype "passive"))
      (node (ref "U802") (pin "20") (pinfunction "PA_OUT_20") (pintype "passive"))
    )
    (net (code "46") (name "Net-(U802-RX_FLT)") (class "Default")
      (node (ref "U802") (pin "11") (pinfunction "RX_FLT_11") (pintype "passive"))
      (node (ref "U803") (pin "2") (pinfunction "IN_2") (pintype "passive"))
    )
    (net (code "47") (name "Net-(U802-TR)") (class "Default")
      (node (ref "C824") (pin "2") (pinfunction "2_2") (pintype "passive"))
      (node (ref "U802") (pin "6") (pinfunction "TR_6") (pintype "passive"))
    )
    (net (code "48") (name "Net-(U802-TX_FLT)") (class "Default")
      (node (ref "R802") (pin "1") (pinfunction "1_1") (pintype "passive"))
      (node (ref "U802") (pin "5") (pinfunction "TX_FLT_5") (pintype "passive"))
    )
    (net (code "49") (name "Net-(U802-TX_IN)") (class "Default")
      (node (ref "C827") (pin "2") (pinfunction "2_2") (pintype "passive"))
      (node (ref "L809") (pin "2") (pinfunction "2_2") (pintype "passive"))
      (node (ref "U802") (pin "16") (pinfunction "TX_IN_16") (pintype "passive"))
    )
    (net (code "50") (name "Net-(U802-VCC0)") (class "Default")
      (node (ref "C819") (pin "2") (pinfunction "2_2") (pintype "passive"))
      (node (ref "L803") (pin "1") (pinfunction "1_1") (pintype "passive"))
      (node (ref "U802") (pin "23") (pinfunction "VCC0_23") (pintype "passive"))
    )
    (net (code "51") (name "Net-(U802-VCC1)") (class "Default")
      (node (ref "C821") (pin "2") (pinfunction "2_2") (pintype "passive"))
      (node (ref "L804") (pin "1") (pinfunction "1_1") (pintype "passive"))
      (node (ref "U802") (pin "24") (pinfunction "VCC1_24") (pintype "passive"))
    )
    (net (code "52") (name "Net-(U802-VCC2)") (class "Default")
      (node (ref "L805") (pin "1") (pinfunction "1_1") (pintype "passive"))
      (node (ref "U802") (pin "21") (pinfunction "VCC2_21") (pintype "passive"))
    )
    (net (code "53") (name "Net-(U805-IN)") (class "Default")
      (node (ref "C816") (pin "2") (pinfunction "2_2") (pintype "passive"))
      (node (ref "U805") (pin "2") (pinfunction "IN_2") (pintype "passive"))
    )
    (net (code "54") (name "Net-(U805-OUT)") (class "Default")
      (node (ref "R807") (pin "2") (pinfunction "2_2") (pintype "passive"))
      (node (ref "R808") (pin "1") (pinfunction "1_1") (pintype "passive"))
      (node (ref "U805") (pin "5") (pinfunction "OUT_5") (pintype "passive"))
    )
    (net (code "55") (name "Net-(U900-VR_ANA1)") (class "Default")
      (node (ref "C903") (pin "2") (pinfunction "2_2") (pintype "passive"))
      (node (ref "U900") (pin "3") (pinfunction "VR_ANA1_3") (pintype "passive"))
    )
    (net (code "56") (name "Net-(U900-VR_ANA2)") (class "Default")
      (node (ref "C907") (pin "2") (pinfunction "2_2") (pintype "passive"))
      (node (ref "U900") (pin "25") (pinfunction "VR_ANA2_25") (pintype "passive"))
    )
    (net (code "57") (name "Net-(U900-VR_DIG)") (class "Default")
      (node (ref "C904") (pin "1") (pinfunction "1_1") (pintype "passive"))
      (node (ref "U900") (pin "5") (pinfunction "VR_DIG_5") (pintype "passive"))
    )
    (net (code "58") (name "Net-(U900-VR_PA)") (class "Default")
      (node (ref "C905") (pin "1") (pinfunction "1_1") (pintype "passive"))
      (node (ref "U900") (pin "1") (pinfunction "VR_PA_1") (pintype "passive"))
    )
    (net (code "59") (name "Net-(U900-XTB)") (class "Default")
      (node (ref "C901") (pin "1") (pinfunction "1_1") (pintype "passive"))
      (node (ref "U900") (pin "8") (pinfunction "XTB_8") (pintype "passive"))
    )
    (net (code "60") (name "Net-(Y800-VCC)") (class "Default")
      (node (ref "C815") (pin "2") (pinfunction "2_2") (pintype "passive"))
      (node (ref "FB801") (pin "2") (pinfunction "2_2") (pintype "passive"))
      (node (ref "Y800") (pin "4") (pinfunction "VCC_4") (pintype "passive"))
    )
    (net (code "61") (name "VCCA_A") (class "Default")
      (node (ref "C800") (pin "2") (pinfunction "2_2") (pintype "passive"))
      (node (ref "C806") (pin "2") (pinfunction "2_2") (pintype "passive"))
      (node (ref "C808") (pin "2") (pinfunction "2_2") (pintype "passive"))
      (node (ref "C818") (pin "2") (pinfunction "2_2") (pintype "passive"))
      (node (ref "FB801") (pin "1") (pinfunction "1_1") (pintype "passive"))
      (node (ref "L803") (pin "2") (pinfunction "2_2") (pintype "passive"))
      (node (ref "U800") (pin "16") (pinfunction "VBAT2_16") (pintype "passive"))
      (node (ref "U800") (pin "2") (pinfunction "VBAT1_2") (pintype "passive"))
      (node (ref "U800") (pin "32") (pinfunction "VBAT3_32") (pintype "passive"))
    )
    (net (code "62") (name "VCCA_B") (class "Default")
      (node (ref "C900") (pin "2") (pinfunction "2_2") (pintype "passive"))
      (node (ref "C906") (pin "2") (pinfunction "2_2") (pintype "passive"))
      (node (ref "C908") (pin "2") (pinfunction "2_2") (pintype "passive"))
      (node (ref "U900") (pin "16") (pinfunction "VBAT2_16") (pintype "passive"))
      (node (ref "U900") (pin "2") (pinfunction "VBAT1_2") (pintype "passive"))
      (node (ref "U900") (pin "32") (pinfunction "VBAT3_32") (pintype "passive"))
    )
    (net (code "63") (name "VCC_FEM") (class "Default")
      (node (ref "C820") (pin "2") (pinfunction "2_2") (pintype "passive"))
      (node (ref "C822") (pin "2") (pinfunction "2_2") (pintype "passive"))
      (node (ref "C823") (pin "2") (pinfunction "2_2") (pintype "passive"))
      (node (ref "FB802") (pin "2") (pinfunction "2_2") (pintype "passive"))
      (node (ref "L804") (pin "2") (pinfunction "2_2") (pintype "passive"))
      (node (ref "L805") (pin "2") (pinfunction "2_2") (pintype "passive"))
    )
    (net (code "64") (name "VCC_FEM_1") (class "Default")
      (node (ref "FB802") (pin "1") (pinfunction "1_1") (pintype "passive"))
    )
    (net (code "65") (name "unconnected-(U800-CLK_OUT-Pad10)") (class "Default")
      (node (ref "U800") (pin "10") (pinfunction "CLK_OUT_10") (pintype "passive+no_connect"))
    )
    (net (code "66") (name "unconnected-(U800-DIO0-Pad21)") (class "Default")
      (node (ref "U800") (pin "21") (pinfunction "DIO0_21") (pintype "passive+no_connect"))
    )
    (net (code "67") (name "unconnected-(U800-DIO1-Pad22)") (class "Default")
      (node (ref "U800") (pin "22") (pinfunction "DIO1_22") (pintype "passive+no_connect"))
    )
    (net (code "68") (name "unconnected-(U800-DIO2-Pad23)") (class "Default")
      (node (ref "U800") (pin "23") (pinfunction "DIO2_23") (pintype "passive+no_connect"))
    )
    (net (code "69") (name "unconnected-(U800-DIO3-Pad24)") (class "Default")
      (node (ref "U800") (pin "24") (pinfunction "DIO3_24") (pintype "passive+no_connect"))
    )
    (net (code "70") (name "unconnected-(U800-XTA-Pad6)") (class "Default")
      (node (ref "U800") (pin "6") (pinfunction "XTA_6") (pintype "passive+no_connect"))
    )
    (net (code "71") (name "unconnected-(U802-NC-Pad19)") (class "Default")
      (node (ref "U802") (pin "19") (pinfunction "NC_19") (pintype "passive+no_connect"))
    )
    (net (code "72") (name "unconnected-(U802-NC-Pad22)") (class "Default")
      (node (ref "U802") (pin "22") (pinfunction "NC_22") (pintype "passive+no_connect"))
    )
    (net (code "73") (name "unconnected-(U900-CLK_IN-Pad11)") (class "Default")
      (node (ref "U900") (pin "11") (pinfunction "CLK_IN_11") (pintype "passive+no_connect"))
    )
    (net (code "74") (name "unconnected-(U900-DIO0-Pad21)") (class "Default")
      (node (ref "U900") (pin "21") (pinfunction "DIO0_21") (pintype "passive+no_connect"))
    )
    (net (code "75") (name "unconnected-(U900-DIO1-Pad22)") (class "Default")
      (node (ref "U900") (pin "22") (pinfunction "DIO1_22") (pintype "passive+no_connect"))
    )
    (net (code "76") (name "unconnected-(U900-DIO2-Pad23)") (class "Default")
      (node (ref "U900") (pin "23") (pinfunction "DIO2_23") (pintype "passive+no_connect"))
    )
    (net (code "77") (name "unconnected-(U900-DIO3-Pad24)") (class "Default")
      (node (ref "U900") (pin "24") (pinfunction "DIO3_24") (pintype "passive+no_connect"))
    )
    (net (code "78") (name "unconnected-(U900-RF_ON-Pad29)") (class "Default")
      (node (ref "U900") (pin "29") (pinfunction "RF_ON_29") (pintype "passive+no_connect"))
    )
    (net (code "79") (name "unconnected-(U900-RF_OP-Pad30)") (class "Default")
      (node (ref "U900") (pin "30") (pinfunction "RF_OP_30") (pintype "passive+no_connect"))
    )
    (net (code "80") (name "unconnected-(U900-XTA-Pad6)") (class "Default")
      (node (ref "U900") (pin "6") (pinfunction "XTA_6") (pintype "passive+no_connect"))
    )
  )
)
